# rc2014_8085.net
KiCad netlist of a schematic drawn in EAGLE
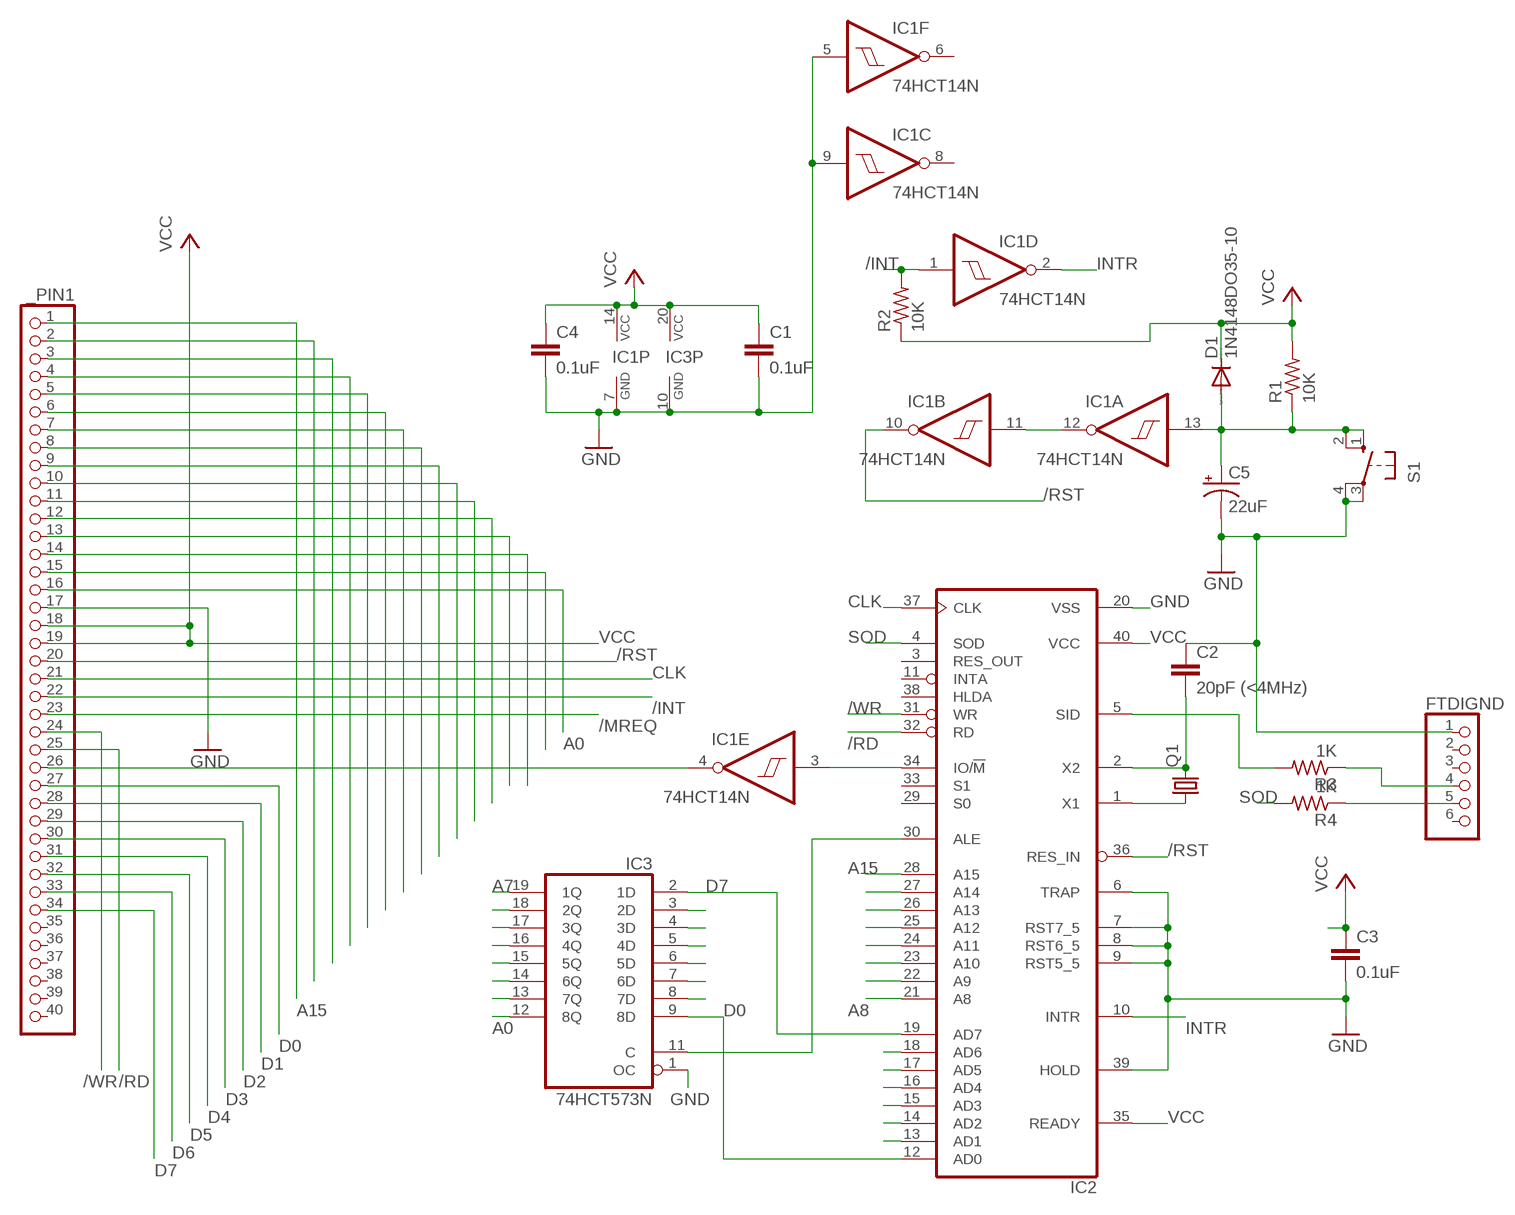
[diagram p0: schematic, sheet 1]

(export (version "E")
  (design (tool "Eeschema 10.0.6"))
  (components
    (comp (ref "C1")
      (value "0.1uF")
      (footprint "eagle-import:C050-024X044")
      (libsource (lib "eagle-import") (part "C-EU050-024X044"))
    )
    (comp (ref "C2")
      (value "20pF (<4MHz)")
      (footprint "eagle-import:C050-024X044")
      (libsource (lib "eagle-import") (part "C-EU050-024X044"))
    )
    (comp (ref "C3")
      (value "0.1uF")
      (footprint "eagle-import:C050-024X044")
      (libsource (lib "eagle-import") (part "C-EU050-024X044"))
    )
    (comp (ref "C4")
      (value "0.1uF")
      (footprint "eagle-import:C050-024X044")
      (libsource (lib "eagle-import") (part "C-EU050-024X044"))
    )
    (comp (ref "C5")
      (value "22uF")
      (footprint "eagle-import:TAP5-80")
      (libsource (lib "eagle-import") (part "CPOL-USTAP5-80"))
    )
    (comp (ref "D1")
      (value "1N4148DO35-10")
      (footprint "eagle-import:DO35-10")
      (libsource (lib "eagle-import") (part "1N4148DO35-10"))
    )
    (comp (ref "FTDIGND")
      (value "PINHD-1X6")
      (footprint "eagle-import:1X06")
      (libsource (lib "eagle-import") (part "PINHD-1X6"))
    )
    (comp (ref "IC1")
      (value "74HCT14N")
      (footprint "eagle-import:DIL14")
      (libsource (lib "eagle-import") (part "7414NHCT"))
    )
    (comp (ref "IC2")
      (value "8085")
      (footprint "eagle-import:DIL40")
      (libsource (lib "eagle-import") (part "8085"))
    )
    (comp (ref "IC3")
      (value "74HCT573N")
      (footprint "eagle-import:DIL20")
      (libsource (lib "eagle-import") (part "74573NHCT"))
    )
    (comp (ref "Q1")
      (value "CRYSTALHC49S")
      (footprint "eagle-import:HC49_S")
      (libsource (lib "eagle-import") (part "CRYSTALHC49S"))
    )
    (comp (ref "R1")
      (value "10K")
      (footprint "eagle-import:0207_10")
      (libsource (lib "eagle-import") (part "R-US_0207/10"))
    )
    (comp (ref "R2")
      (value "10K")
      (footprint "eagle-import:0207_10")
      (libsource (lib "eagle-import") (part "R-US_0207/10"))
    )
    (comp (ref "R3")
      (value "1K")
      (footprint "eagle-import:0207_10")
      (libsource (lib "eagle-import") (part "R-US_0207/10"))
    )
    (comp (ref "R4")
      (value "1K")
      (footprint "eagle-import:0207_10")
      (libsource (lib "eagle-import") (part "R-US_0207/10"))
    )
    (comp (ref "S1")
      (value "10-XX")
      (footprint "eagle-import:B3F-10XX")
      (fields (field (name "MPN") "B3F-1000"))
      (libsource (lib "eagle-import") (part "10-XX"))
    )
    (comp (ref "_PIN1")
      (value "PINHD-1X40")
      (footprint "eagle-import:1X40")
      (libsource (lib "eagle-import") (part "PINHD-1X40"))
    )
  )
  (nets
    (net (code "1") (name "/A0") (class "Default")
      (node (ref "IC3") (pin "12") (pinfunction "8Q_12") (pintype "tri_state"))
      (node (ref "_PIN1") (pin "16") (pinfunction "16_16") (pintype "passive"))
    )
    (net (code "2") (name "/A1") (class "Default")
      (node (ref "IC3") (pin "13") (pinfunction "7Q_13") (pintype "tri_state"))
      (node (ref "_PIN1") (pin "15") (pinfunction "15_15") (pintype "passive"))
    )
    (net (code "3") (name "/A2") (class "Default")
      (node (ref "IC3") (pin "14") (pinfunction "6Q_14") (pintype "tri_state"))
      (node (ref "_PIN1") (pin "14") (pinfunction "14_14") (pintype "passive"))
    )
    (net (code "4") (name "/A3") (class "Default")
      (node (ref "IC3") (pin "15") (pinfunction "5Q_15") (pintype "tri_state"))
      (node (ref "_PIN1") (pin "13") (pinfunction "13_13") (pintype "passive"))
    )
    (net (code "5") (name "/A4") (class "Default")
      (node (ref "IC3") (pin "16") (pinfunction "4Q_16") (pintype "tri_state"))
      (node (ref "_PIN1") (pin "12") (pinfunction "12_12") (pintype "passive"))
    )
    (net (code "6") (name "/A5") (class "Default")
      (node (ref "IC3") (pin "17") (pinfunction "3Q_17") (pintype "tri_state"))
      (node (ref "_PIN1") (pin "11") (pinfunction "11_11") (pintype "passive"))
    )
    (net (code "7") (name "/A6") (class "Default")
      (node (ref "IC3") (pin "18") (pinfunction "2Q_18") (pintype "tri_state"))
      (node (ref "_PIN1") (pin "10") (pinfunction "10_10") (pintype "passive"))
    )
    (net (code "8") (name "/A7") (class "Default")
      (node (ref "IC3") (pin "19") (pinfunction "1Q_19") (pintype "tri_state"))
      (node (ref "_PIN1") (pin "9") (pinfunction "9_9") (pintype "passive"))
    )
    (net (code "9") (name "/A8") (class "Default")
      (node (ref "IC2") (pin "21") (pinfunction "A8_21") (pintype "output"))
      (node (ref "_PIN1") (pin "8") (pinfunction "8_8") (pintype "passive"))
    )
    (net (code "10") (name "/A9") (class "Default")
      (node (ref "IC2") (pin "22") (pinfunction "A9_22") (pintype "output"))
      (node (ref "_PIN1") (pin "7") (pinfunction "7_7") (pintype "passive"))
    )
    (net (code "11") (name "/A10") (class "Default")
      (node (ref "IC2") (pin "23") (pinfunction "A10_23") (pintype "output"))
      (node (ref "_PIN1") (pin "6") (pinfunction "6_6") (pintype "passive"))
    )
    (net (code "12") (name "/A11") (class "Default")
      (node (ref "IC2") (pin "24") (pinfunction "A11_24") (pintype "output"))
      (node (ref "_PIN1") (pin "5") (pinfunction "5_5") (pintype "passive"))
    )
    (net (code "13") (name "/A12") (class "Default")
      (node (ref "IC2") (pin "25") (pinfunction "A12_25") (pintype "output"))
      (node (ref "_PIN1") (pin "4") (pinfunction "4_4") (pintype "passive"))
    )
    (net (code "14") (name "/A13") (class "Default")
      (node (ref "IC2") (pin "26") (pinfunction "A13_26") (pintype "output"))
      (node (ref "_PIN1") (pin "3") (pinfunction "3_3") (pintype "passive"))
    )
    (net (code "15") (name "/A14") (class "Default")
      (node (ref "IC2") (pin "27") (pinfunction "A14_27") (pintype "output"))
      (node (ref "_PIN1") (pin "2") (pinfunction "2_2") (pintype "passive"))
    )
    (net (code "16") (name "/A15") (class "Default")
      (node (ref "IC2") (pin "28") (pinfunction "A15_28") (pintype "output"))
      (node (ref "_PIN1") (pin "1") (pinfunction "1_1") (pintype "passive"))
    )
    (net (code "17") (name "/CLK") (class "Default")
      (node (ref "IC2") (pin "37") (pinfunction "CLK_37") (pintype "output"))
      (node (ref "_PIN1") (pin "21") (pinfunction "21_21") (pintype "passive"))
    )
    (net (code "18") (name "/D0") (class "Default")
      (node (ref "IC2") (pin "12") (pinfunction "AD0_12") (pintype "bidirectional"))
      (node (ref "IC3") (pin "9") (pinfunction "8D_9") (pintype "input"))
      (node (ref "_PIN1") (pin "27") (pinfunction "27_27") (pintype "passive"))
    )
    (net (code "19") (name "/D1") (class "Default")
      (node (ref "IC2") (pin "13") (pinfunction "AD1_13") (pintype "bidirectional"))
      (node (ref "IC3") (pin "8") (pinfunction "7D_8") (pintype "input"))
      (node (ref "_PIN1") (pin "28") (pinfunction "28_28") (pintype "passive"))
    )
    (net (code "20") (name "/D2") (class "Default")
      (node (ref "IC2") (pin "14") (pinfunction "AD2_14") (pintype "bidirectional"))
      (node (ref "IC3") (pin "7") (pinfunction "6D_7") (pintype "input"))
      (node (ref "_PIN1") (pin "29") (pinfunction "29_29") (pintype "passive"))
    )
    (net (code "21") (name "/D3") (class "Default")
      (node (ref "IC2") (pin "15") (pinfunction "AD3_15") (pintype "bidirectional"))
      (node (ref "IC3") (pin "6") (pinfunction "5D_6") (pintype "input"))
      (node (ref "_PIN1") (pin "30") (pinfunction "30_30") (pintype "passive"))
    )
    (net (code "22") (name "/D4") (class "Default")
      (node (ref "IC2") (pin "16") (pinfunction "AD4_16") (pintype "bidirectional"))
      (node (ref "IC3") (pin "5") (pinfunction "4D_5") (pintype "input"))
      (node (ref "_PIN1") (pin "31") (pinfunction "31_31") (pintype "passive"))
    )
    (net (code "23") (name "/D5") (class "Default")
      (node (ref "IC2") (pin "17") (pinfunction "AD5_17") (pintype "bidirectional"))
      (node (ref "IC3") (pin "4") (pinfunction "3D_4") (pintype "input"))
      (node (ref "_PIN1") (pin "32") (pinfunction "32_32") (pintype "passive"))
    )
    (net (code "24") (name "/D6") (class "Default")
      (node (ref "IC2") (pin "18") (pinfunction "AD6_18") (pintype "bidirectional"))
      (node (ref "IC3") (pin "3") (pinfunction "2D_3") (pintype "input"))
      (node (ref "_PIN1") (pin "33") (pinfunction "33_33") (pintype "passive"))
    )
    (net (code "25") (name "/D7") (class "Default")
      (node (ref "IC2") (pin "19") (pinfunction "AD7_19") (pintype "bidirectional"))
      (node (ref "IC3") (pin "2") (pinfunction "1D_2") (pintype "input"))
      (node (ref "_PIN1") (pin "34") (pinfunction "34_34") (pintype "passive"))
    )
    (net (code "26") (name "/INTR") (class "Default")
      (node (ref "IC1") (pin "2") (pinfunction "O_2") (pintype "output"))
      (node (ref "IC2") (pin "10") (pinfunction "INTR_10") (pintype "input"))
    )
    (net (code "27") (name "/SOD") (class "Default")
      (node (ref "IC2") (pin "4") (pinfunction "SOD_4") (pintype "output"))
      (node (ref "R4") (pin "2") (pinfunction "2_2") (pintype "passive"))
    )
    (net (code "28") (name "/{slash}INT") (class "Default")
      (node (ref "IC1") (pin "1") (pinfunction "I_1") (pintype "input"))
      (node (ref "R2") (pin "2") (pinfunction "2_2") (pintype "passive"))
      (node (ref "_PIN1") (pin "22") (pinfunction "22_22") (pintype "passive"))
    )
    (net (code "29") (name "/{slash}MREQ") (class "Default")
      (node (ref "IC1") (pin "3") (pinfunction "I_3") (pintype "input"))
      (node (ref "IC2") (pin "34") (pinfunction "IO/~{M}_34") (pintype "output"))
      (node (ref "_PIN1") (pin "23") (pinfunction "23_23") (pintype "passive"))
    )
    (net (code "30") (name "/{slash}RD") (class "Default")
      (node (ref "IC2") (pin "32") (pinfunction "RD_32") (pintype "output"))
      (node (ref "_PIN1") (pin "25") (pinfunction "25_25") (pintype "passive"))
    )
    (net (code "31") (name "/{slash}RST") (class "Default")
      (node (ref "IC1") (pin "10") (pinfunction "O_10") (pintype "output"))
      (node (ref "IC2") (pin "36") (pinfunction "RES_IN_36") (pintype "input"))
      (node (ref "_PIN1") (pin "20") (pinfunction "20_20") (pintype "passive"))
    )
    (net (code "32") (name "/{slash}WR") (class "Default")
      (node (ref "IC2") (pin "31") (pinfunction "WR_31") (pintype "output"))
      (node (ref "_PIN1") (pin "24") (pinfunction "24_24") (pintype "passive"))
    )
    (net (code "33") (name "GND") (class "Default")
      (node (ref "C1") (pin "2") (pinfunction "2_2") (pintype "passive"))
      (node (ref "C2") (pin "1") (pinfunction "1_1") (pintype "passive"))
      (node (ref "C3") (pin "2") (pinfunction "2_2") (pintype "passive"))
      (node (ref "C4") (pin "2") (pinfunction "2_2") (pintype "passive"))
      (node (ref "C5") (pin "-") (pinfunction "-_-") (pintype "passive"))
      (node (ref "FTDIGND") (pin "1") (pinfunction "1_1") (pintype "passive"))
      (node (ref "IC1") (pin "5") (pinfunction "I_5") (pintype "input"))
      (node (ref "IC1") (pin "7") (pinfunction "GND_7") (pintype "power_in"))
      (node (ref "IC1") (pin "9") (pinfunction "I_9") (pintype "input"))
      (node (ref "IC2") (pin "20") (pinfunction "VSS_20") (pintype "power_in"))
      (node (ref "IC2") (pin "39") (pinfunction "HOLD_39") (pintype "input"))
      (node (ref "IC2") (pin "6") (pinfunction "TRAP_6") (pintype "input"))
      (node (ref "IC2") (pin "7") (pinfunction "RST7_5_7") (pintype "input"))
      (node (ref "IC2") (pin "8") (pinfunction "RST6_5_8") (pintype "input"))
      (node (ref "IC2") (pin "9") (pinfunction "RST5_5_9") (pintype "input"))
      (node (ref "IC3") (pin "1") (pinfunction "OC_1") (pintype "input"))
      (node (ref "IC3") (pin "10") (pinfunction "GND_10") (pintype "power_in"))
      (node (ref "S1") (pin "3") (pinfunction "P_3") (pintype "passive"))
      (node (ref "S1") (pin "4") (pinfunction "P1_4") (pintype "passive"))
      (node (ref "_PIN1") (pin "17") (pinfunction "17_17") (pintype "passive"))
    )
    (net (code "34") (name "Net-(FTDIGND-Pad4)") (class "Default")
      (node (ref "FTDIGND") (pin "4") (pinfunction "4_4") (pintype "passive"))
      (node (ref "R3") (pin "1") (pinfunction "1_1") (pintype "passive"))
    )
    (net (code "35") (name "Net-(FTDIGND-Pad5)") (class "Default")
      (node (ref "FTDIGND") (pin "5") (pinfunction "5_5") (pintype "passive"))
      (node (ref "R4") (pin "1") (pinfunction "1_1") (pintype "passive"))
    )
    (net (code "36") (name "Net-(IC1A-I)") (class "Default")
      (node (ref "C5") (pin "+") (pinfunction "+_+") (pintype "passive"))
      (node (ref "D1") (pin "A") (pinfunction "A_A") (pintype "passive"))
      (node (ref "IC1") (pin "13") (pinfunction "I_13") (pintype "input"))
      (node (ref "R1") (pin "1") (pinfunction "1_1") (pintype "passive"))
      (node (ref "S1") (pin "1") (pinfunction "S_1") (pintype "passive"))
      (node (ref "S1") (pin "2") (pinfunction "S1_2") (pintype "passive"))
    )
    (net (code "37") (name "Net-(IC1A-O)") (class "Default")
      (node (ref "IC1") (pin "11") (pinfunction "I_11") (pintype "input"))
      (node (ref "IC1") (pin "12") (pinfunction "O_12") (pintype "output"))
    )
    (net (code "38") (name "Net-(IC1E-O)") (class "Default")
      (node (ref "IC1") (pin "4") (pinfunction "O_4") (pintype "output"))
      (node (ref "_PIN1") (pin "26") (pinfunction "26_26") (pintype "passive"))
    )
    (net (code "39") (name "Net-(IC2-ALE)") (class "Default")
      (node (ref "IC2") (pin "30") (pinfunction "ALE_30") (pintype "output"))
      (node (ref "IC3") (pin "11") (pinfunction "C_11") (pintype "input"))
    )
    (net (code "40") (name "Net-(IC2-SID)") (class "Default")
      (node (ref "IC2") (pin "5") (pinfunction "SID_5") (pintype "input"))
      (node (ref "R3") (pin "2") (pinfunction "2_2") (pintype "passive"))
    )
    (net (code "41") (name "Net-(IC2-X1)") (class "Default")
      (node (ref "IC2") (pin "1") (pinfunction "X1_1") (pintype "input"))
      (node (ref "Q1") (pin "1") (pinfunction "1_1") (pintype "passive"))
    )
    (net (code "42") (name "Net-(IC2-X2)") (class "Default")
      (node (ref "C2") (pin "2") (pinfunction "2_2") (pintype "passive"))
      (node (ref "IC2") (pin "2") (pinfunction "X2_2") (pintype "input"))
      (node (ref "Q1") (pin "2") (pinfunction "2_2") (pintype "passive"))
    )
    (net (code "43") (name "VCC") (class "Default")
      (node (ref "C1") (pin "1") (pinfunction "1_1") (pintype "passive"))
      (node (ref "C3") (pin "1") (pinfunction "1_1") (pintype "passive"))
      (node (ref "C4") (pin "1") (pinfunction "1_1") (pintype "passive"))
      (node (ref "D1") (pin "C") (pinfunction "C_C") (pintype "passive"))
      (node (ref "IC1") (pin "14") (pinfunction "VCC_14") (pintype "power_in"))
      (node (ref "IC2") (pin "35") (pinfunction "READY_35") (pintype "input"))
      (node (ref "IC2") (pin "40") (pinfunction "VCC_40") (pintype "power_in"))
      (node (ref "IC3") (pin "20") (pinfunction "VCC_20") (pintype "power_in"))
      (node (ref "R1") (pin "2") (pinfunction "2_2") (pintype "passive"))
      (node (ref "R2") (pin "1") (pinfunction "1_1") (pintype "passive"))
      (node (ref "_PIN1") (pin "18") (pinfunction "18_18") (pintype "passive"))
      (node (ref "_PIN1") (pin "19") (pinfunction "19_19") (pintype "passive"))
    )
    (net (code "44") (name "unconnected-(FTDIGND-Pad2)") (class "Default")
      (node (ref "FTDIGND") (pin "2") (pinfunction "2_2") (pintype "passive"))
    )
    (net (code "45") (name "unconnected-(FTDIGND-Pad3)") (class "Default")
      (node (ref "FTDIGND") (pin "3") (pinfunction "3_3") (pintype "passive"))
    )
    (net (code "46") (name "unconnected-(FTDIGND-Pad6)") (class "Default")
      (node (ref "FTDIGND") (pin "6") (pinfunction "6_6") (pintype "passive"))
    )
    (net (code "47") (name "unconnected-(IC1C-O-Pad8)") (class "Default")
      (node (ref "IC1") (pin "8") (pinfunction "O_8") (pintype "output"))
    )
    (net (code "48") (name "unconnected-(IC1F-O-Pad6)") (class "Default")
      (node (ref "IC1") (pin "6") (pinfunction "O_6") (pintype "output"))
    )
    (net (code "49") (name "unconnected-(IC2-HLDA-Pad38)") (class "Default")
      (node (ref "IC2") (pin "38") (pinfunction "HLDA_38") (pintype "output"))
    )
    (net (code "50") (name "unconnected-(IC2-INTA-Pad11)") (class "Default")
      (node (ref "IC2") (pin "11") (pinfunction "INTA_11") (pintype "output"))
    )
    (net (code "51") (name "unconnected-(IC2-RES_OUT-Pad3)") (class "Default")
      (node (ref "IC2") (pin "3") (pinfunction "RES_OUT_3") (pintype "output"))
    )
    (net (code "52") (name "unconnected-(IC2-S0-Pad29)") (class "Default")
      (node (ref "IC2") (pin "29") (pinfunction "S0_29") (pintype "output"))
    )
    (net (code "53") (name "unconnected-(IC2-S1-Pad33)") (class "Default")
      (node (ref "IC2") (pin "33") (pinfunction "S1_33") (pintype "output"))
    )
    (net (code "54") (name "unconnected-(_PIN1-Pad35)") (class "Default")
      (node (ref "_PIN1") (pin "35") (pinfunction "35_35") (pintype "passive"))
    )
    (net (code "55") (name "unconnected-(_PIN1-Pad36)") (class "Default")
      (node (ref "_PIN1") (pin "36") (pinfunction "36_36") (pintype "passive"))
    )
    (net (code "56") (name "unconnected-(_PIN1-Pad37)") (class "Default")
      (node (ref "_PIN1") (pin "37") (pinfunction "37_37") (pintype "passive"))
    )
    (net (code "57") (name "unconnected-(_PIN1-Pad38)") (class "Default")
      (node (ref "_PIN1") (pin "38") (pinfunction "38_38") (pintype "passive"))
    )
    (net (code "58") (name "unconnected-(_PIN1-Pad39)") (class "Default")
      (node (ref "_PIN1") (pin "39") (pinfunction "39_39") (pintype "passive"))
    )
    (net (code "59") (name "unconnected-(_PIN1-Pad40)") (class "Default")
      (node (ref "_PIN1") (pin "40") (pinfunction "40_40") (pintype "passive"))
    )
  )
)
